# LightShaker-3.net
KiCad netlist of a schematic drawn in EAGLE
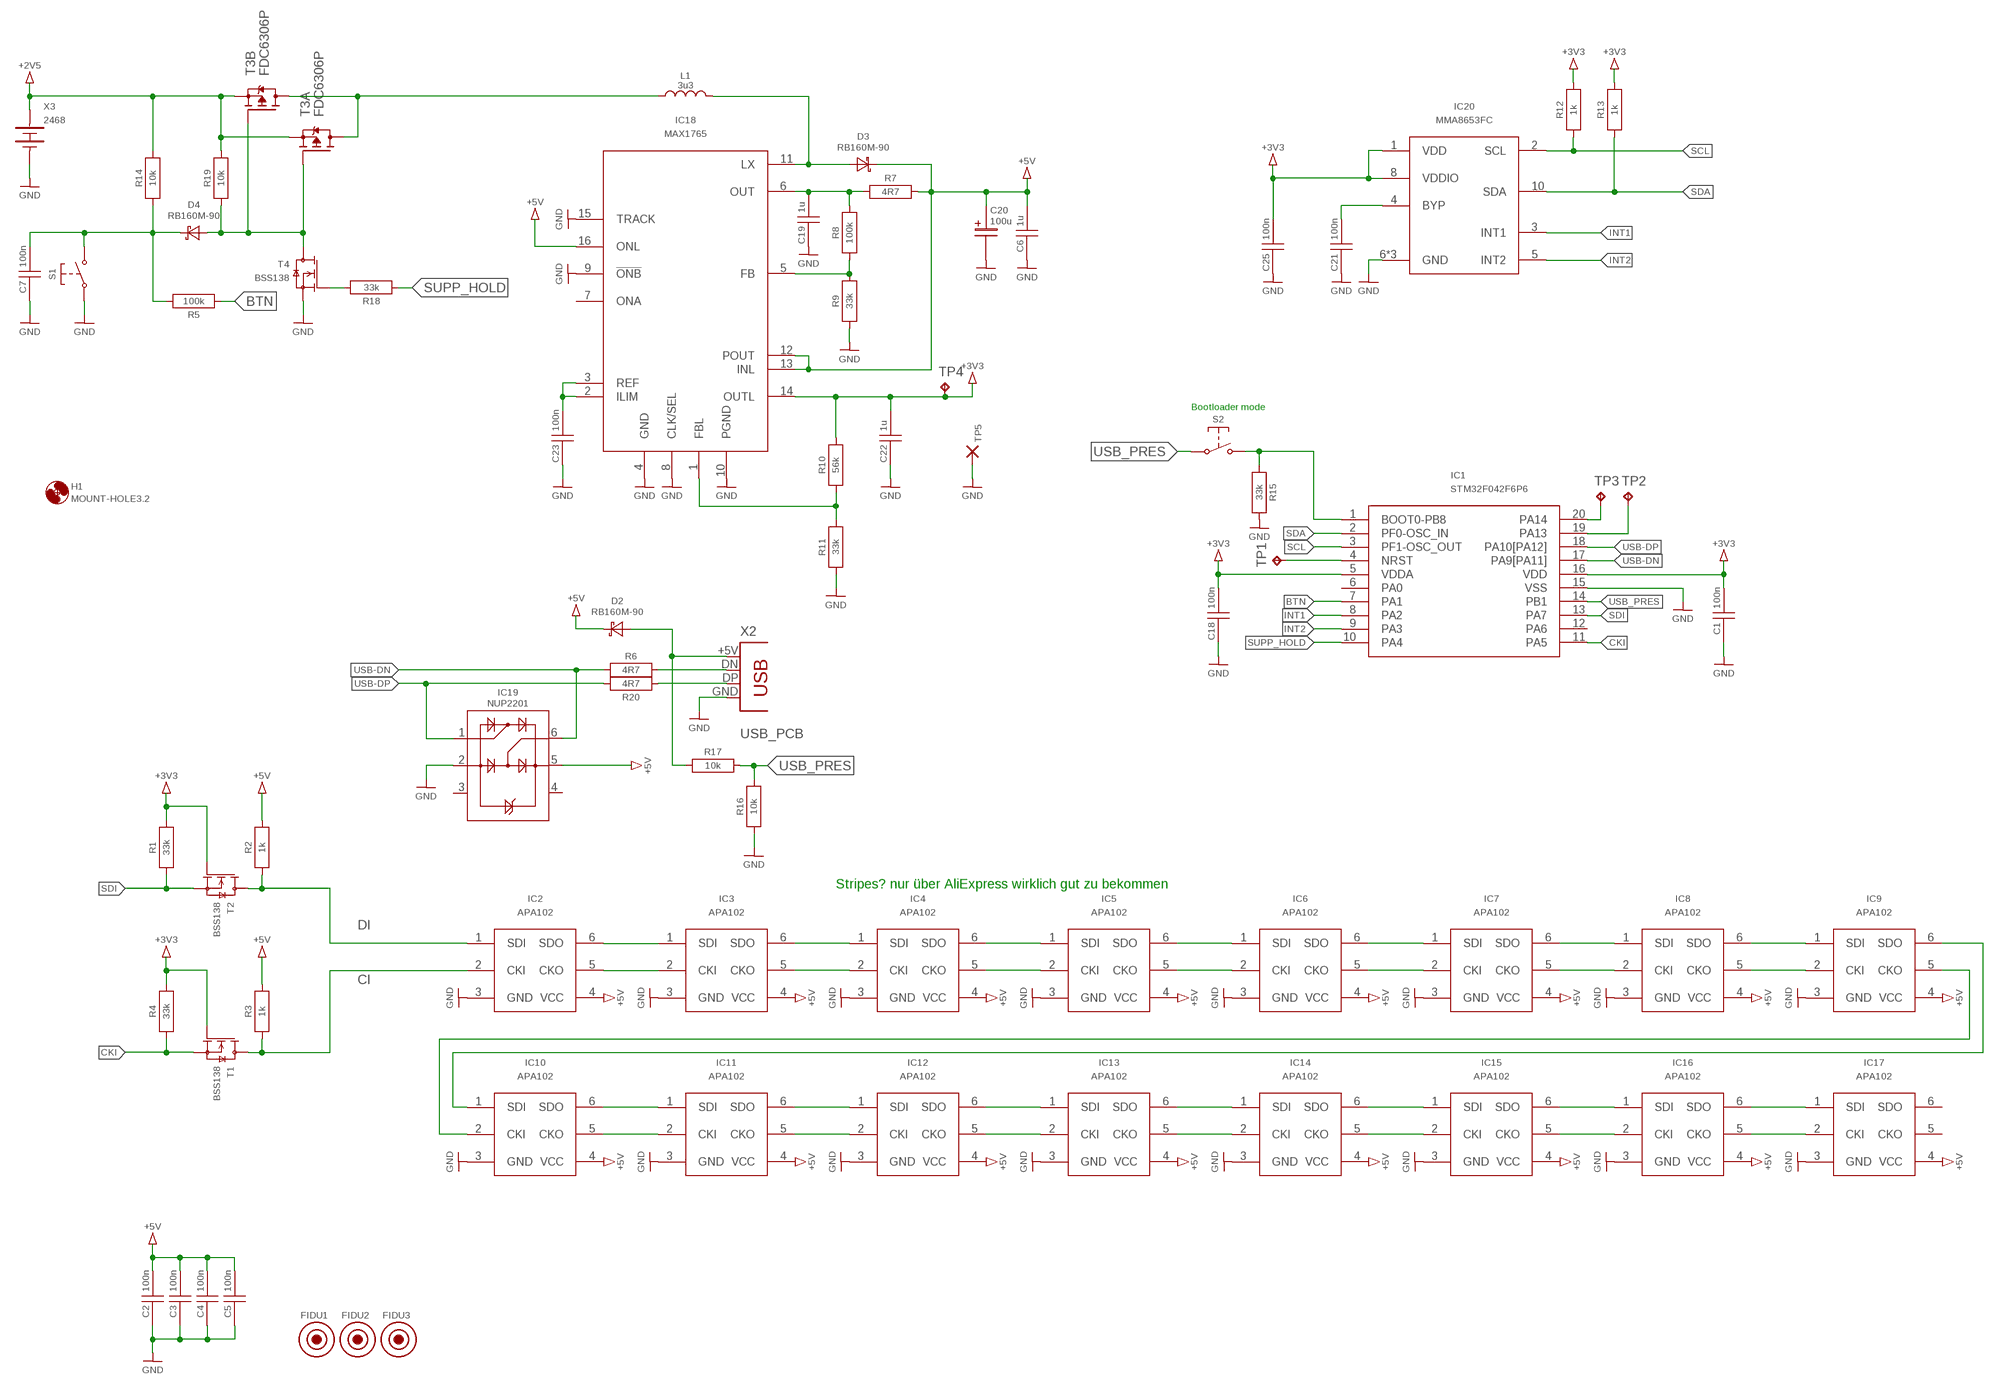
[diagram p0: schematic, sheet 1]

(export (version "E")
  (design (tool "Eeschema 10.0.6"))
  (components
    (comp (ref "C1")
      (value "100n")
      (footprint "eagle-import:SM_1206")
      (fields (field (name "MECHPART") "FALSE") (field (name "PARTNR") "E0001400"))
      (libsource (lib "eagle-import") (part "C1206"))
    )
    (comp (ref "C2")
      (value "100n")
      (footprint "eagle-import:SM_1206")
      (fields (field (name "MECHPART") "FALSE") (field (name "PARTNR") "E0001400"))
      (libsource (lib "eagle-import") (part "C1206"))
    )
    (comp (ref "C3")
      (value "100n")
      (footprint "eagle-import:SM_1206")
      (fields (field (name "MECHPART") "FALSE") (field (name "PARTNR") "E0001400"))
      (libsource (lib "eagle-import") (part "C1206"))
    )
    (comp (ref "C4")
      (value "100n")
      (footprint "eagle-import:SM_1206")
      (fields (field (name "MECHPART") "FALSE") (field (name "PARTNR") "E0001400"))
      (libsource (lib "eagle-import") (part "C1206"))
    )
    (comp (ref "C5")
      (value "100n")
      (footprint "eagle-import:SM_1206")
      (fields (field (name "MECHPART") "FALSE") (field (name "PARTNR") "E0001400"))
      (libsource (lib "eagle-import") (part "C1206"))
    )
    (comp (ref "C6")
      (value "1u")
      (footprint "eagle-import:SM_1206")
      (fields (field (name "MECHPART") "FALSE") (field (name "PARTNR") "E0487200"))
      (libsource (lib "eagle-import") (part "C1206"))
    )
    (comp (ref "C7")
      (value "100n")
      (footprint "eagle-import:SM_1206")
      (fields (field (name "MECHPART") "FALSE") (field (name "PARTNR") "E0001400"))
      (libsource (lib "eagle-import") (part "C1206"))
    )
    (comp (ref "C18")
      (value "100n")
      (footprint "eagle-import:SM_1206")
      (fields (field (name "MECHPART") "FALSE") (field (name "PARTNR") "E0001400"))
      (libsource (lib "eagle-import") (part "C1206"))
    )
    (comp (ref "C19")
      (value "1u")
      (footprint "eagle-import:SM_1206")
      (fields (field (name "MECHPART") "FALSE") (field (name "PARTNR") "E0487200"))
      (libsource (lib "eagle-import") (part "C1206"))
    )
    (comp (ref "C20")
      (value "100u")
      (footprint "eagle-import:SM_SIZE-D")
      (fields (field (name "MECHPART") "FALSE") (field (name "PARTNR") "E0242200"))
      (libsource (lib "eagle-import") (part "CPOLSIZE-D"))
    )
    (comp (ref "C21")
      (value "100n")
      (footprint "eagle-import:SM_1206")
      (fields (field (name "MECHPART") "FALSE") (field (name "PARTNR") "E0001400"))
      (libsource (lib "eagle-import") (part "C1206"))
    )
    (comp (ref "C22")
      (value "1u")
      (footprint "eagle-import:SM_1206")
      (fields (field (name "MECHPART") "FALSE") (field (name "PARTNR") "E0487200"))
      (libsource (lib "eagle-import") (part "C1206"))
    )
    (comp (ref "C23")
      (value "100n")
      (footprint "eagle-import:SM_1206")
      (fields (field (name "MECHPART") "FALSE") (field (name "PARTNR") "E0001400"))
      (libsource (lib "eagle-import") (part "C1206"))
    )
    (comp (ref "C25")
      (value "100n")
      (footprint "eagle-import:SM_1206")
      (fields (field (name "MECHPART") "FALSE") (field (name "PARTNR") "E0001400"))
      (libsource (lib "eagle-import") (part "C1206"))
    )
    (comp (ref "D2")
      (value "RB160M-90")
      (footprint "eagle-import:SM_SOD123_POL")
      (libsource (lib "eagle-import") (part "RB160M-90"))
    )
    (comp (ref "D3")
      (value "RB160M-90")
      (footprint "eagle-import:SM_SOD123_POL")
      (libsource (lib "eagle-import") (part "RB160M-90"))
    )
    (comp (ref "D4")
      (value "RB160M-90")
      (footprint "eagle-import:SM_SOD123_POL")
      (libsource (lib "eagle-import") (part "RB160M-90"))
    )
    (comp (ref "FIDU1")
      (value "FIDU_ROUND_NEW")
      (footprint "eagle-import:FIDUCIAL_LOETSTOPP")
      (libsource (lib "eagle-import") (part "FIDU_ROUND_NEW"))
    )
    (comp (ref "FIDU2")
      (value "FIDU_ROUND_NEW")
      (footprint "eagle-import:FIDUCIAL_LOETSTOPP")
      (libsource (lib "eagle-import") (part "FIDU_ROUND_NEW"))
    )
    (comp (ref "FIDU3")
      (value "FIDU_ROUND_NEW")
      (footprint "eagle-import:FIDUCIAL_LOETSTOPP")
      (libsource (lib "eagle-import") (part "FIDU_ROUND_NEW"))
    )
    (comp (ref "H1")
      (value "MOUNT-HOLE3.2")
      (footprint "eagle-import:3.2")
      (libsource (lib "eagle-import") (part "MOUNT-HOLE3.2"))
    )
    (comp (ref "IC1")
      (value "STM32F042F6P6")
      (footprint "eagle-import:SM_TSSOP20")
      (libsource (lib "eagle-import") (part "STM32F042F6P6"))
    )
    (comp (ref "IC2")
      (value "APA102")
      (footprint "eagle-import:SM_LED_PLCC6")
      (libsource (lib "eagle-import") (part "APA102"))
    )
    (comp (ref "IC3")
      (value "APA102")
      (footprint "eagle-import:SM_LED_PLCC6")
      (libsource (lib "eagle-import") (part "APA102"))
    )
    (comp (ref "IC4")
      (value "APA102")
      (footprint "eagle-import:SM_LED_PLCC6")
      (libsource (lib "eagle-import") (part "APA102"))
    )
    (comp (ref "IC5")
      (value "APA102")
      (footprint "eagle-import:SM_LED_PLCC6")
      (libsource (lib "eagle-import") (part "APA102"))
    )
    (comp (ref "IC6")
      (value "APA102")
      (footprint "eagle-import:SM_LED_PLCC6")
      (libsource (lib "eagle-import") (part "APA102"))
    )
    (comp (ref "IC7")
      (value "APA102")
      (footprint "eagle-import:SM_LED_PLCC6")
      (libsource (lib "eagle-import") (part "APA102"))
    )
    (comp (ref "IC8")
      (value "APA102")
      (footprint "eagle-import:SM_LED_PLCC6")
      (libsource (lib "eagle-import") (part "APA102"))
    )
    (comp (ref "IC9")
      (value "APA102")
      (footprint "eagle-import:SM_LED_PLCC6")
      (libsource (lib "eagle-import") (part "APA102"))
    )
    (comp (ref "IC10")
      (value "APA102")
      (footprint "eagle-import:SM_LED_PLCC6")
      (libsource (lib "eagle-import") (part "APA102"))
    )
    (comp (ref "IC11")
      (value "APA102")
      (footprint "eagle-import:SM_LED_PLCC6")
      (libsource (lib "eagle-import") (part "APA102"))
    )
    (comp (ref "IC12")
      (value "APA102")
      (footprint "eagle-import:SM_LED_PLCC6")
      (libsource (lib "eagle-import") (part "APA102"))
    )
    (comp (ref "IC13")
      (value "APA102")
      (footprint "eagle-import:SM_LED_PLCC6")
      (libsource (lib "eagle-import") (part "APA102"))
    )
    (comp (ref "IC14")
      (value "APA102")
      (footprint "eagle-import:SM_LED_PLCC6")
      (libsource (lib "eagle-import") (part "APA102"))
    )
    (comp (ref "IC15")
      (value "APA102")
      (footprint "eagle-import:SM_LED_PLCC6")
      (libsource (lib "eagle-import") (part "APA102"))
    )
    (comp (ref "IC16")
      (value "APA102")
      (footprint "eagle-import:SM_LED_PLCC6")
      (libsource (lib "eagle-import") (part "APA102"))
    )
    (comp (ref "IC17")
      (value "APA102")
      (footprint "eagle-import:SM_LED_PLCC6")
      (libsource (lib "eagle-import") (part "APA102"))
    )
    (comp (ref "IC18")
      (value "MAX1765")
      (footprint "eagle-import:SM_QSOP16")
      (libsource (lib "eagle-import") (part "MAX1765"))
    )
    (comp (ref "IC19")
      (value "NUP2201")
      (footprint "eagle-import:TSOP6")
      (libsource (lib "eagle-import") (part "NUP2201"))
    )
    (comp (ref "IC20")
      (value "MMA8653FC")
      (footprint "eagle-import:SM_DFN10")
      (libsource (lib "eagle-import") (part "MMA8653FC"))
    )
    (comp (ref "L1")
      (value "3u3")
      (footprint "eagle-import:SM_L_MOS6020")
      (libsource (lib "eagle-import") (part "L_MOS6020"))
    )
    (comp (ref "R1")
      (value "33k")
      (footprint "eagle-import:SM_1206")
      (fields (field (name "MECHPART") "FALSE") (field (name "PARTNR") "E0149800"))
      (libsource (lib "eagle-import") (part "R1206"))
    )
    (comp (ref "R2")
      (value "1k")
      (footprint "eagle-import:SM_1206")
      (fields (field (name "MECHPART") "FALSE") (field (name "PARTNR") "E0002500"))
      (libsource (lib "eagle-import") (part "R1206"))
    )
    (comp (ref "R3")
      (value "1k")
      (footprint "eagle-import:SM_1206")
      (fields (field (name "MECHPART") "FALSE") (field (name "PARTNR") "E0002500"))
      (libsource (lib "eagle-import") (part "R1206"))
    )
    (comp (ref "R4")
      (value "33k")
      (footprint "eagle-import:SM_1206")
      (fields (field (name "MECHPART") "FALSE") (field (name "PARTNR") "E0149800"))
      (libsource (lib "eagle-import") (part "R1206"))
    )
    (comp (ref "R5")
      (value "100k")
      (footprint "eagle-import:SM_1206")
      (fields (field (name "MECHPART") "FALSE"))
      (libsource (lib "eagle-import") (part "R1206"))
    )
    (comp (ref "R6")
      (value "4R7")
      (footprint "eagle-import:SM_1206")
      (fields (field (name "MECHPART") "FALSE"))
      (libsource (lib "eagle-import") (part "R1206"))
    )
    (comp (ref "R7")
      (value "4R7")
      (footprint "eagle-import:SM_1206")
      (fields (field (name "MECHPART") "FALSE") (field (name "PARTNR") "E0821300"))
      (libsource (lib "eagle-import") (part "R1206"))
    )
    (comp (ref "R8")
      (value "100k")
      (footprint "eagle-import:SM_1206")
      (fields (field (name "MECHPART") "FALSE") (field (name "PARTNR") "E0002800"))
      (libsource (lib "eagle-import") (part "R1206"))
    )
    (comp (ref "R9")
      (value "33k")
      (footprint "eagle-import:SM_1206")
      (fields (field (name "MECHPART") "FALSE") (field (name "PARTNR") "E0149800"))
      (libsource (lib "eagle-import") (part "R1206"))
    )
    (comp (ref "R10")
      (value "56k")
      (footprint "eagle-import:SM_1206")
      (fields (field (name "MECHPART") "FALSE"))
      (libsource (lib "eagle-import") (part "R1206"))
    )
    (comp (ref "R11")
      (value "33k")
      (footprint "eagle-import:SM_1206")
      (fields (field (name "MECHPART") "FALSE") (field (name "PARTNR") "E0149800"))
      (libsource (lib "eagle-import") (part "R1206"))
    )
    (comp (ref "R12")
      (value "1k")
      (footprint "eagle-import:SM_1206")
      (fields (field (name "MECHPART") "FALSE") (field (name "PARTNR") "E0002500"))
      (libsource (lib "eagle-import") (part "R1206"))
    )
    (comp (ref "R13")
      (value "1k")
      (footprint "eagle-import:SM_1206")
      (fields (field (name "MECHPART") "FALSE") (field (name "PARTNR") "E0002500"))
      (libsource (lib "eagle-import") (part "R1206"))
    )
    (comp (ref "R14")
      (value "10k")
      (footprint "eagle-import:SM_1206")
      (fields (field (name "MECHPART") "FALSE") (field (name "PARTNR") "E0002700"))
      (libsource (lib "eagle-import") (part "R1206"))
    )
    (comp (ref "R15")
      (value "33k")
      (footprint "eagle-import:SM_1206")
      (fields (field (name "MECHPART") "FALSE") (field (name "PARTNR") "E0149800"))
      (libsource (lib "eagle-import") (part "R1206"))
    )
    (comp (ref "R16")
      (value "10k")
      (footprint "eagle-import:SM_1206")
      (fields (field (name "MECHPART") "FALSE") (field (name "PARTNR") "E0002700"))
      (libsource (lib "eagle-import") (part "R1206"))
    )
    (comp (ref "R17")
      (value "10k")
      (footprint "eagle-import:SM_1206")
      (fields (field (name "MECHPART") "FALSE") (field (name "PARTNR") "E0002700"))
      (libsource (lib "eagle-import") (part "R1206"))
    )
    (comp (ref "R18")
      (value "33k")
      (footprint "eagle-import:SM_1206")
      (fields (field (name "MECHPART") "FALSE") (field (name "PARTNR") "E0149800"))
      (libsource (lib "eagle-import") (part "R1206"))
    )
    (comp (ref "R19")
      (value "10k")
      (footprint "eagle-import:SM_1206")
      (fields (field (name "MECHPART") "FALSE") (field (name "PARTNR") "E0002800"))
      (libsource (lib "eagle-import") (part "R1206"))
    )
    (comp (ref "R20")
      (value "4R7")
      (footprint "eagle-import:SM_1206")
      (fields (field (name "MECHPART") "FALSE"))
      (libsource (lib "eagle-import") (part "R1206"))
    )
    (comp (ref "S1")
      (value "PUSH-BUTTON_SMD")
      (footprint "eagle-import:PUSH-BUTTON_SMD")
      (libsource (lib "eagle-import") (part "PUSH-BUTTON_SMD"))
    )
    (comp (ref "S2")
      (value "PUSH-BUTTON_SMD")
      (footprint "eagle-import:PUSH-BUTTON_SMD")
      (libsource (lib "eagle-import") (part "PUSH-BUTTON_SMD"))
    )
    (comp (ref "T1")
      (value "BSS138")
      (footprint "eagle-import:SM_SOT23")
      (libsource (lib "eagle-import") (part "BSS138"))
    )
    (comp (ref "T2")
      (value "BSS138")
      (footprint "eagle-import:SM_SOT23")
      (libsource (lib "eagle-import") (part "BSS138"))
    )
    (comp (ref "T3")
      (value "FDC6306P")
      (footprint "eagle-import:TSOP6")
      (fields (field (name "PARTNR") "E0662100"))
      (libsource (lib "eagle-import") (part "FDC6306P"))
    )
    (comp (ref "T4")
      (value "BSS138")
      (footprint "eagle-import:SM_SOT23")
      (libsource (lib "eagle-import") (part "BSS138"))
    )
    (comp (ref "TP1")
      (value "TPTP12R")
      (footprint "eagle-import:TP12R")
      (libsource (lib "eagle-import") (part "TPTP12R"))
    )
    (comp (ref "TP2")
      (value "TPTP12R")
      (footprint "eagle-import:TP12R")
      (libsource (lib "eagle-import") (part "TPTP12R"))
    )
    (comp (ref "TP3")
      (value "TPTP12R")
      (footprint "eagle-import:TP12R")
      (libsource (lib "eagle-import") (part "TPTP12R"))
    )
    (comp (ref "TP4")
      (value "TPTP12R")
      (footprint "eagle-import:TP12R")
      (libsource (lib "eagle-import") (part "TPTP12R"))
    )
    (comp (ref "TP5")
      (value "CHECKER_1206")
      (footprint "eagle-import:SM_RCW_1206")
      (libsource (lib "eagle-import") (part "CHECKER_1206"))
    )
    (comp (ref "X2")
      (value "USB_PCB")
      (footprint "eagle-import:USB_PCB")
      (libsource (lib "eagle-import") (part "USB_PCB"))
    )
    (comp (ref "X3")
      (value "2468")
      (footprint "eagle-import:2468")
      (libsource (lib "eagle-import") (part "2468"))
    )
  )
  (nets
    (net (code "1") (name "+2V5") (class "Default")
      (node (ref "R14") (pin "2") (pinfunction "2_2") (pintype "bidirectional"))
      (node (ref "R19") (pin "2") (pinfunction "2_2") (pintype "bidirectional"))
      (node (ref "T3") (pin "2") (pinfunction "S_2") (pintype "passive"))
      (node (ref "T3") (pin "5") (pinfunction "S_5") (pintype "passive"))
      (node (ref "X3") (pin "POS") (pinfunction "POS_POS") (pintype "bidirectional"))
    )
    (net (code "2") (name "+3V3") (class "Default")
      (node (ref "C1") (pin "2") (pinfunction "2_2") (pintype "bidirectional"))
      (node (ref "C18") (pin "2") (pinfunction "2_2") (pintype "bidirectional"))
      (node (ref "C22") (pin "2") (pinfunction "2_2") (pintype "bidirectional"))
      (node (ref "C25") (pin "2") (pinfunction "2_2") (pintype "bidirectional"))
      (node (ref "IC1") (pin "16") (pinfunction "VDD_16") (pintype "bidirectional"))
      (node (ref "IC1") (pin "5") (pinfunction "VDDA_5") (pintype "bidirectional"))
      (node (ref "IC18") (pin "14") (pinfunction "OUTL_14") (pintype "bidirectional"))
      (node (ref "IC20") (pin "1") (pinfunction "VDD_1") (pintype "bidirectional"))
      (node (ref "IC20") (pin "8") (pinfunction "VDDIO_8") (pintype "bidirectional"))
      (node (ref "R1") (pin "2") (pinfunction "2_2") (pintype "bidirectional"))
      (node (ref "R10") (pin "2") (pinfunction "2_2") (pintype "bidirectional"))
      (node (ref "R12") (pin "2") (pinfunction "2_2") (pintype "bidirectional"))
      (node (ref "R13") (pin "2") (pinfunction "2_2") (pintype "bidirectional"))
      (node (ref "R4") (pin "2") (pinfunction "2_2") (pintype "bidirectional"))
      (node (ref "T1") (pin "1") (pinfunction "G_1") (pintype "bidirectional"))
      (node (ref "T2") (pin "1") (pinfunction "G_1") (pintype "bidirectional"))
      (node (ref "TP4") (pin "TP") (pinfunction "TP_TP") (pintype "input"))
    )
    (net (code "3") (name "+5V") (class "Default")
      (node (ref "C2") (pin "2") (pinfunction "2_2") (pintype "bidirectional"))
      (node (ref "C20") (pin "POS") (pinfunction "POS_POS") (pintype "bidirectional"))
      (node (ref "C3") (pin "2") (pinfunction "2_2") (pintype "bidirectional"))
      (node (ref "C4") (pin "2") (pinfunction "2_2") (pintype "bidirectional"))
      (node (ref "C5") (pin "2") (pinfunction "2_2") (pintype "bidirectional"))
      (node (ref "C6") (pin "2") (pinfunction "2_2") (pintype "bidirectional"))
      (node (ref "D2") (pin "C") (pinfunction "C_C") (pintype "bidirectional"))
      (node (ref "D3") (pin "C") (pinfunction "C_C") (pintype "bidirectional"))
      (node (ref "IC10") (pin "4") (pinfunction "VCC_4") (pintype "bidirectional"))
      (node (ref "IC11") (pin "4") (pinfunction "VCC_4") (pintype "bidirectional"))
      (node (ref "IC12") (pin "4") (pinfunction "VCC_4") (pintype "bidirectional"))
      (node (ref "IC13") (pin "4") (pinfunction "VCC_4") (pintype "bidirectional"))
      (node (ref "IC14") (pin "4") (pinfunction "VCC_4") (pintype "bidirectional"))
      (node (ref "IC15") (pin "4") (pinfunction "VCC_4") (pintype "bidirectional"))
      (node (ref "IC16") (pin "4") (pinfunction "VCC_4") (pintype "bidirectional"))
      (node (ref "IC17") (pin "4") (pinfunction "VCC_4") (pintype "bidirectional"))
      (node (ref "IC18") (pin "12") (pinfunction "POUT_12") (pintype "bidirectional"))
      (node (ref "IC18") (pin "13") (pinfunction "INL_13") (pintype "bidirectional"))
      (node (ref "IC18") (pin "16") (pinfunction "ONL_16") (pintype "bidirectional"))
      (node (ref "IC19") (pin "5") (pinfunction "VP_5") (pintype "bidirectional"))
      (node (ref "IC2") (pin "4") (pinfunction "VCC_4") (pintype "bidirectional"))
      (node (ref "IC3") (pin "4") (pinfunction "VCC_4") (pintype "bidirectional"))
      (node (ref "IC4") (pin "4") (pinfunction "VCC_4") (pintype "bidirectional"))
      (node (ref "IC5") (pin "4") (pinfunction "VCC_4") (pintype "bidirectional"))
      (node (ref "IC6") (pin "4") (pinfunction "VCC_4") (pintype "bidirectional"))
      (node (ref "IC7") (pin "4") (pinfunction "VCC_4") (pintype "bidirectional"))
      (node (ref "IC8") (pin "4") (pinfunction "VCC_4") (pintype "bidirectional"))
      (node (ref "IC9") (pin "4") (pinfunction "VCC_4") (pintype "bidirectional"))
      (node (ref "R2") (pin "2") (pinfunction "2_2") (pintype "bidirectional"))
      (node (ref "R3") (pin "2") (pinfunction "2_2") (pintype "bidirectional"))
      (node (ref "R7") (pin "2") (pinfunction "2_2") (pintype "bidirectional"))
    )
    (net (code "4") (name "/CI") (class "Default")
      (node (ref "IC2") (pin "2") (pinfunction "CKI_2") (pintype "bidirectional"))
      (node (ref "R3") (pin "1") (pinfunction "1_1") (pintype "bidirectional"))
      (node (ref "T1") (pin "3") (pinfunction "D_3") (pintype "bidirectional"))
    )
    (net (code "5") (name "/DI") (class "Default")
      (node (ref "IC2") (pin "1") (pinfunction "SDI_1") (pintype "bidirectional"))
      (node (ref "R2") (pin "1") (pinfunction "1_1") (pintype "bidirectional"))
      (node (ref "T2") (pin "3") (pinfunction "D_3") (pintype "bidirectional"))
    )
    (net (code "6") (name "BTN") (class "Default")
      (node (ref "IC1") (pin "7") (pinfunction "PA1_7") (pintype "bidirectional"))
      (node (ref "R5") (pin "1") (pinfunction "1_1") (pintype "bidirectional"))
    )
    (net (code "7") (name "CKI") (class "Default")
      (node (ref "IC1") (pin "11") (pinfunction "PA5_11") (pintype "bidirectional"))
      (node (ref "R4") (pin "1") (pinfunction "1_1") (pintype "bidirectional"))
      (node (ref "T1") (pin "2") (pinfunction "S_2") (pintype "bidirectional"))
    )
    (net (code "8") (name "GND") (class "Default")
      (node (ref "C1") (pin "1") (pinfunction "1_1") (pintype "bidirectional"))
      (node (ref "C18") (pin "1") (pinfunction "1_1") (pintype "bidirectional"))
      (node (ref "C19") (pin "1") (pinfunction "1_1") (pintype "bidirectional"))
      (node (ref "C2") (pin "1") (pinfunction "1_1") (pintype "bidirectional"))
      (node (ref "C20") (pin "NEG") (pinfunction "NEG_NEG") (pintype "bidirectional"))
      (node (ref "C21") (pin "1") (pinfunction "1_1") (pintype "bidirectional"))
      (node (ref "C22") (pin "1") (pinfunction "1_1") (pintype "bidirectional"))
      (node (ref "C23") (pin "1") (pinfunction "1_1") (pintype "bidirectional"))
      (node (ref "C25") (pin "1") (pinfunction "1_1") (pintype "bidirectional"))
      (node (ref "C3") (pin "1") (pinfunction "1_1") (pintype "bidirectional"))
      (node (ref "C4") (pin "1") (pinfunction "1_1") (pintype "bidirectional"))
      (node (ref "C5") (pin "1") (pinfunction "1_1") (pintype "bidirectional"))
      (node (ref "C6") (pin "1") (pinfunction "1_1") (pintype "bidirectional"))
      (node (ref "C7") (pin "1") (pinfunction "1_1") (pintype "bidirectional"))
      (node (ref "IC1") (pin "15") (pinfunction "VSS_15") (pintype "bidirectional"))
      (node (ref "IC10") (pin "3") (pinfunction "GND_3") (pintype "bidirectional"))
      (node (ref "IC11") (pin "3") (pinfunction "GND_3") (pintype "bidirectional"))
      (node (ref "IC12") (pin "3") (pinfunction "GND_3") (pintype "bidirectional"))
      (node (ref "IC13") (pin "3") (pinfunction "GND_3") (pintype "bidirectional"))
      (node (ref "IC14") (pin "3") (pinfunction "GND_3") (pintype "bidirectional"))
      (node (ref "IC15") (pin "3") (pinfunction "GND_3") (pintype "bidirectional"))
      (node (ref "IC16") (pin "3") (pinfunction "GND_3") (pintype "bidirectional"))
      (node (ref "IC17") (pin "3") (pinfunction "GND_3") (pintype "bidirectional"))
      (node (ref "IC18") (pin "10") (pinfunction "PGND_10") (pintype "bidirectional"))
      (node (ref "IC18") (pin "15") (pinfunction "TRACK_15") (pintype "bidirectional"))
      (node (ref "IC18") (pin "4") (pinfunction "GND_4") (pintype "bidirectional"))
      (node (ref "IC18") (pin "8") (pinfunction "CLK/SEL_8") (pintype "bidirectional"))
      (node (ref "IC18") (pin "9") (pinfunction "~{ONB}_9") (pintype "bidirectional"))
      (node (ref "IC19") (pin "2") (pinfunction "GND_2") (pintype "bidirectional"))
      (node (ref "IC2") (pin "3") (pinfunction "GND_3") (pintype "bidirectional"))
      (node (ref "IC20") (pin "6") (pinfunction "GND_6") (pintype "bidirectional"))
      (node (ref "IC20") (pin "7") (pinfunction "GND_7") (pintype "bidirectional"))
      (node (ref "IC20") (pin "9") (pinfunction "GND_9") (pintype "bidirectional"))
      (node (ref "IC3") (pin "3") (pinfunction "GND_3") (pintype "bidirectional"))
      (node (ref "IC4") (pin "3") (pinfunction "GND_3") (pintype "bidirectional"))
      (node (ref "IC5") (pin "3") (pinfunction "GND_3") (pintype "bidirectional"))
      (node (ref "IC6") (pin "3") (pinfunction "GND_3") (pintype "bidirectional"))
      (node (ref "IC7") (pin "3") (pinfunction "GND_3") (pintype "bidirectional"))
      (node (ref "IC8") (pin "3") (pinfunction "GND_3") (pintype "bidirectional"))
      (node (ref "IC9") (pin "3") (pinfunction "GND_3") (pintype "bidirectional"))
      (node (ref "R11") (pin "1") (pinfunction "1_1") (pintype "bidirectional"))
      (node (ref "R15") (pin "2") (pinfunction "2_2") (pintype "bidirectional"))
      (node (ref "R16") (pin "1") (pinfunction "1_1") (pintype "bidirectional"))
      (node (ref "R9") (pin "1") (pinfunction "1_1") (pintype "bidirectional"))
      (node (ref "S1") (pin "1") (pinfunction "P_1") (pintype "passive"))
      (node (ref "S1") (pin "2") (pinfunction "P_2") (pintype "passive"))
      (node (ref "T4") (pin "2") (pinfunction "S_2") (pintype "bidirectional"))
      (node (ref "TP5") (pin "1") (pinfunction "P_1") (pintype "passive"))
      (node (ref "X2") (pin "GND") (pinfunction "GND_GND") (pintype "passive"))
      (node (ref "X3") (pin "NEG") (pinfunction "NEG_NEG") (pintype "bidirectional"))
    )
    (net (code "9") (name "INT1") (class "Default")
      (node (ref "IC1") (pin "8") (pinfunction "PA2_8") (pintype "bidirectional"))
      (node (ref "IC20") (pin "3") (pinfunction "INT1_3") (pintype "bidirectional"))
    )
    (net (code "10") (name "INT2") (class "Default")
      (node (ref "IC1") (pin "9") (pinfunction "PA3_9") (pintype "bidirectional"))
      (node (ref "IC20") (pin "5") (pinfunction "INT2_5") (pintype "bidirectional"))
    )
    (net (code "11") (name "Net-(C7-Pad2)") (class "Default")
      (node (ref "C7") (pin "2") (pinfunction "2_2") (pintype "bidirectional"))
      (node (ref "D4") (pin "C") (pinfunction "C_C") (pintype "bidirectional"))
      (node (ref "R14") (pin "1") (pinfunction "1_1") (pintype "bidirectional"))
      (node (ref "R5") (pin "2") (pinfunction "2_2") (pintype "bidirectional"))
      (node (ref "S1") (pin "3") (pinfunction "S_3") (pintype "passive"))
      (node (ref "S1") (pin "4") (pinfunction "S_4") (pintype "passive"))
    )
    (net (code "12") (name "Net-(D2-PadA)") (class "Default")
      (node (ref "D2") (pin "A") (pinfunction "A_A") (pintype "bidirectional"))
      (node (ref "R17") (pin "1") (pinfunction "1_1") (pintype "bidirectional"))
      (node (ref "X2") (pin "+5V") (pinfunction "+5V_+5V") (pintype "passive"))
    )
    (net (code "13") (name "Net-(IC1-BOOT0-PB8)") (class "Default")
      (node (ref "IC1") (pin "1") (pinfunction "BOOT0-PB8_1") (pintype "bidirectional"))
      (node (ref "R15") (pin "1") (pinfunction "1_1") (pintype "bidirectional"))
      (node (ref "S2") (pin "3") (pinfunction "S_3") (pintype "passive"))
      (node (ref "S2") (pin "4") (pinfunction "S_4") (pintype "passive"))
    )
    (net (code "14") (name "Net-(IC1-NRST)") (class "Default")
      (node (ref "IC1") (pin "4") (pinfunction "NRST_4") (pintype "bidirectional"))
      (node (ref "TP1") (pin "TP") (pinfunction "TP_TP") (pintype "input"))
    )
    (net (code "15") (name "Net-(IC1-PA13)") (class "Default")
      (node (ref "IC1") (pin "19") (pinfunction "PA13_19") (pintype "bidirectional"))
      (node (ref "TP2") (pin "TP") (pinfunction "TP_TP") (pintype "input"))
    )
    (net (code "16") (name "Net-(IC1-PA14)") (class "Default")
      (node (ref "IC1") (pin "20") (pinfunction "PA14_20") (pintype "bidirectional"))
      (node (ref "TP3") (pin "TP") (pinfunction "TP_TP") (pintype "input"))
    )
    (net (code "17") (name "Net-(IC2-CKO)") (class "Default")
      (node (ref "IC2") (pin "5") (pinfunction "CKO_5") (pintype "bidirectional"))
      (node (ref "IC3") (pin "2") (pinfunction "CKI_2") (pintype "bidirectional"))
    )
    (net (code "18") (name "Net-(IC2-SDO)") (class "Default")
      (node (ref "IC2") (pin "6") (pinfunction "SDO_6") (pintype "bidirectional"))
      (node (ref "IC3") (pin "1") (pinfunction "SDI_1") (pintype "bidirectional"))
    )
    (net (code "19") (name "Net-(IC3-CKO)") (class "Default")
      (node (ref "IC3") (pin "5") (pinfunction "CKO_5") (pintype "bidirectional"))
      (node (ref "IC4") (pin "2") (pinfunction "CKI_2") (pintype "bidirectional"))
    )
    (net (code "20") (name "Net-(IC3-SDO)") (class "Default")
      (node (ref "IC3") (pin "6") (pinfunction "SDO_6") (pintype "bidirectional"))
      (node (ref "IC4") (pin "1") (pinfunction "SDI_1") (pintype "bidirectional"))
    )
    (net (code "21") (name "Net-(IC4-CKO)") (class "Default")
      (node (ref "IC4") (pin "5") (pinfunction "CKO_5") (pintype "bidirectional"))
      (node (ref "IC5") (pin "2") (pinfunction "CKI_2") (pintype "bidirectional"))
    )
    (net (code "22") (name "Net-(IC4-SDO)") (class "Default")
      (node (ref "IC4") (pin "6") (pinfunction "SDO_6") (pintype "bidirectional"))
      (node (ref "IC5") (pin "1") (pinfunction "SDI_1") (pintype "bidirectional"))
    )
    (net (code "23") (name "Net-(IC5-CKO)") (class "Default")
      (node (ref "IC5") (pin "5") (pinfunction "CKO_5") (pintype "bidirectional"))
      (node (ref "IC6") (pin "2") (pinfunction "CKI_2") (pintype "bidirectional"))
    )
    (net (code "24") (name "Net-(IC5-SDO)") (class "Default")
      (node (ref "IC5") (pin "6") (pinfunction "SDO_6") (pintype "bidirectional"))
      (node (ref "IC6") (pin "1") (pinfunction "SDI_1") (pintype "bidirectional"))
    )
    (net (code "25") (name "Net-(IC6-CKO)") (class "Default")
      (node (ref "IC6") (pin "5") (pinfunction "CKO_5") (pintype "bidirectional"))
      (node (ref "IC7") (pin "2") (pinfunction "CKI_2") (pintype "bidirectional"))
    )
    (net (code "26") (name "Net-(IC6-SDO)") (class "Default")
      (node (ref "IC6") (pin "6") (pinfunction "SDO_6") (pintype "bidirectional"))
      (node (ref "IC7") (pin "1") (pinfunction "SDI_1") (pintype "bidirectional"))
    )
    (net (code "27") (name "Net-(IC7-CKO)") (class "Default")
      (node (ref "IC7") (pin "5") (pinfunction "CKO_5") (pintype "bidirectional"))
      (node (ref "IC8") (pin "2") (pinfunction "CKI_2") (pintype "bidirectional"))
    )
    (net (code "28") (name "Net-(IC7-SDO)") (class "Default")
      (node (ref "IC7") (pin "6") (pinfunction "SDO_6") (pintype "bidirectional"))
      (node (ref "IC8") (pin "1") (pinfunction "SDI_1") (pintype "bidirectional"))
    )
    (net (code "29") (name "Net-(IC8-CKO)") (class "Default")
      (node (ref "IC8") (pin "5") (pinfunction "CKO_5") (pintype "bidirectional"))
      (node (ref "IC9") (pin "2") (pinfunction "CKI_2") (pintype "bidirectional"))
    )
    (net (code "30") (name "Net-(IC8-SDO)") (class "Default")
      (node (ref "IC8") (pin "6") (pinfunction "SDO_6") (pintype "bidirectional"))
      (node (ref "IC9") (pin "1") (pinfunction "SDI_1") (pintype "bidirectional"))
    )
    (net (code "31") (name "Net-(IC10-CKI)") (class "Default")
      (node (ref "IC10") (pin "2") (pinfunction "CKI_2") (pintype "bidirectional"))
      (node (ref "IC9") (pin "5") (pinfunction "CKO_5") (pintype "bidirectional"))
    )
    (net (code "32") (name "Net-(IC10-CKO)") (class "Default")
      (node (ref "IC10") (pin "5") (pinfunction "CKO_5") (pintype "bidirectional"))
      (node (ref "IC11") (pin "2") (pinfunction "CKI_2") (pintype "bidirectional"))
    )
    (net (code "33") (name "Net-(IC10-SDI)") (class "Default")
      (node (ref "IC10") (pin "1") (pinfunction "SDI_1") (pintype "bidirectional"))
      (node (ref "IC9") (pin "6") (pinfunction "SDO_6") (pintype "bidirectional"))
    )
    (net (code "34") (name "Net-(IC10-SDO)") (class "Default")
      (node (ref "IC10") (pin "6") (pinfunction "SDO_6") (pintype "bidirectional"))
      (node (ref "IC11") (pin "1") (pinfunction "SDI_1") (pintype "bidirectional"))
    )
    (net (code "35") (name "Net-(IC11-CKO)") (class "Default")
      (node (ref "IC11") (pin "5") (pinfunction "CKO_5") (pintype "bidirectional"))
      (node (ref "IC12") (pin "2") (pinfunction "CKI_2") (pintype "bidirectional"))
    )
    (net (code "36") (name "Net-(IC11-SDO)") (class "Default")
      (node (ref "IC11") (pin "6") (pinfunction "SDO_6") (pintype "bidirectional"))
      (node (ref "IC12") (pin "1") (pinfunction "SDI_1") (pintype "bidirectional"))
    )
    (net (code "37") (name "Net-(IC12-CKO)") (class "Default")
      (node (ref "IC12") (pin "5") (pinfunction "CKO_5") (pintype "bidirectional"))
      (node (ref "IC13") (pin "2") (pinfunction "CKI_2") (pintype "bidirectional"))
    )
    (net (code "38") (name "Net-(IC12-SDO)") (class "Default")
      (node (ref "IC12") (pin "6") (pinfunction "SDO_6") (pintype "bidirectional"))
      (node (ref "IC13") (pin "1") (pinfunction "SDI_1") (pintype "bidirectional"))
    )
    (net (code "39") (name "Net-(IC13-CKO)") (class "Default")
      (node (ref "IC13") (pin "5") (pinfunction "CKO_5") (pintype "bidirectional"))
      (node (ref "IC14") (pin "2") (pinfunction "CKI_2") (pintype "bidirectional"))
    )
    (net (code "40") (name "Net-(IC13-SDO)") (class "Default")
      (node (ref "IC13") (pin "6") (pinfunction "SDO_6") (pintype "bidirectional"))
      (node (ref "IC14") (pin "1") (pinfunction "SDI_1") (pintype "bidirectional"))
    )
    (net (code "41") (name "Net-(IC14-CKO)") (class "Default")
      (node (ref "IC14") (pin "5") (pinfunction "CKO_5") (pintype "bidirectional"))
      (node (ref "IC15") (pin "2") (pinfunction "CKI_2") (pintype "bidirectional"))
    )
    (net (code "42") (name "Net-(IC14-SDO)") (class "Default")
      (node (ref "IC14") (pin "6") (pinfunction "SDO_6") (pintype "bidirectional"))
      (node (ref "IC15") (pin "1") (pinfunction "SDI_1") (pintype "bidirectional"))
    )
    (net (code "43") (name "Net-(IC15-CKO)") (class "Default")
      (node (ref "IC15") (pin "5") (pinfunction "CKO_5") (pintype "bidirectional"))
      (node (ref "IC16") (pin "2") (pinfunction "CKI_2") (pintype "bidirectional"))
    )
    (net (code "44") (name "Net-(IC15-SDO)") (class "Default")
      (node (ref "IC15") (pin "6") (pinfunction "SDO_6") (pintype "bidirectional"))
      (node (ref "IC16") (pin "1") (pinfunction "SDI_1") (pintype "bidirectional"))
    )
    (net (code "45") (name "Net-(IC16-CKO)") (class "Default")
      (node (ref "IC16") (pin "5") (pinfunction "CKO_5") (pintype "bidirectional"))
      (node (ref "IC17") (pin "2") (pinfunction "CKI_2") (pintype "bidirectional"))
    )
    (net (code "46") (name "Net-(IC16-SDO)") (class "Default")
      (node (ref "IC16") (pin "6") (pinfunction "SDO_6") (pintype "bidirectional"))
      (node (ref "IC17") (pin "1") (pinfunction "SDI_1") (pintype "bidirectional"))
    )
    (net (code "47") (name "Net-(IC18-FB)") (class "Default")
      (node (ref "IC18") (pin "5") (pinfunction "FB_5") (pintype "bidirectional"))
      (node (ref "R8") (pin "1") (pinfunction "1_1") (pintype "bidirectional"))
      (node (ref "R9") (pin "2") (pinfunction "2_2") (pintype "bidirectional"))
    )
    (net (code "48") (name "Net-(IC18-FBL)") (class "Default")
      (node (ref "IC18") (pin "1") (pinfunction "FBL_1") (pintype "bidirectional"))
      (node (ref "R10") (pin "1") (pinfunction "1_1") (pintype "bidirectional"))
      (node (ref "R11") (pin "2") (pinfunction "2_2") (pintype "bidirectional"))
    )
    (net (code "49") (name "Net-(IC18-ILIM)") (class "Default")
      (node (ref "C23") (pin "2") (pinfunction "2_2") (pintype "bidirectional"))
      (node (ref "IC18") (pin "2") (pinfunction "ILIM_2") (pintype "bidirectional"))
      (node (ref "IC18") (pin "3") (pinfunction "REF_3") (pintype "bidirectional"))
    )
    (net (code "50") (name "Net-(IC18-LX)") (class "Default")
      (node (ref "D3") (pin "A") (pinfunction "A_A") (pintype "bidirectional"))
      (node (ref "IC18") (pin "11") (pinfunction "LX_11") (pintype "bidirectional"))
      (node (ref "L1") (pin "2") (pinfunction "2_2") (pintype "bidirectional"))
    )
    (net (code "51") (name "Net-(IC18-OUT)") (class "Default")
      (node (ref "C19") (pin "2") (pinfunction "2_2") (pintype "bidirectional"))
      (node (ref "IC18") (pin "6") (pinfunction "OUT_6") (pintype "bidirectional"))
      (node (ref "R7") (pin "1") (pinfunction "1_1") (pintype "bidirectional"))
      (node (ref "R8") (pin "2") (pinfunction "2_2") (pintype "bidirectional"))
    )
    (net (code "52") (name "Net-(IC20-BYP)") (class "Default")
      (node (ref "C21") (pin "2") (pinfunction "2_2") (pintype "bidirectional"))
      (node (ref "IC20") (pin "4") (pinfunction "BYP_4") (pintype "bidirectional"))
    )
    (net (code "53") (name "Net-(R6-Pad2)") (class "Default")
      (node (ref "R6") (pin "2") (pinfunction "2_2") (pintype "bidirectional"))
      (node (ref "X2") (pin "DN") (pinfunction "DN_DN") (pintype "passive"))
    )
    (net (code "54") (name "Net-(R20-Pad1)") (class "Default")
      (node (ref "R20") (pin "1") (pinfunction "1_1") (pintype "bidirectional"))
      (node (ref "X2") (pin "DP") (pinfunction "DP_DP") (pintype "passive"))
    )
    (net (code "55") (name "Net-(T3A-D)") (class "Default")
      (node (ref "L1") (pin "1") (pinfunction "1_1") (pintype "bidirectional"))
      (node (ref "T3") (pin "4") (pinfunction "D_4") (pintype "passive"))
      (node (ref "T3") (pin "6") (pinfunction "D_6") (pintype "passive"))
    )
    (net (code "56") (name "Net-(T3A-G)") (class "Default")
      (node (ref "D4") (pin "A") (pinfunction "A_A") (pintype "bidirectional"))
      (node (ref "R19") (pin "1") (pinfunction "1_1") (pintype "bidirectional"))
      (node (ref "T3") (pin "1") (pinfunction "G_1") (pintype "passive"))
      (node (ref "T3") (pin "3") (pinfunction "G_3") (pintype "passive"))
      (node (ref "T4") (pin "3") (pinfunction "D_3") (pintype "bidirectional"))
    )
    (net (code "57") (name "Net-(T4-G)") (class "Default")
      (node (ref "R18") (pin "2") (pinfunction "2_2") (pintype "bidirectional"))
      (node (ref "T4") (pin "1") (pinfunction "G_1") (pintype "bidirectional"))
    )
    (net (code "58") (name "SCL") (class "Default")
      (node (ref "IC1") (pin "3") (pinfunction "PF1-OSC_OUT_3") (pintype "bidirectional"))
      (node (ref "IC20") (pin "2") (pinfunction "SCL_2") (pintype "bidirectional"))
      (node (ref "R12") (pin "1") (pinfunction "1_1") (pintype "bidirectional"))
    )
    (net (code "59") (name "SDA") (class "Default")
      (node (ref "IC1") (pin "2") (pinfunction "PF0-OSC_IN_2") (pintype "bidirectional"))
      (node (ref "IC20") (pin "10") (pinfunction "SDA_10") (pintype "bidirectional"))
      (node (ref "R13") (pin "1") (pinfunction "1_1") (pintype "bidirectional"))
    )
    (net (code "60") (name "SDI") (class "Default")
      (node (ref "IC1") (pin "13") (pinfunction "PA7_13") (pintype "bidirectional"))
      (node (ref "R1") (pin "1") (pinfunction "1_1") (pintype "bidirectional"))
      (node (ref "T2") (pin "2") (pinfunction "S_2") (pintype "bidirectional"))
    )
    (net (code "61") (name "SUPP_HOLD") (class "Default")
      (node (ref "IC1") (pin "10") (pinfunction "PA4_10") (pintype "bidirectional"))
      (node (ref "R18") (pin "1") (pinfunction "1_1") (pintype "bidirectional"))
    )
    (net (code "62") (name "USB-DN") (class "Default")
      (node (ref "IC1") (pin "17") (pinfunction "PA9[PA11]_17") (pintype "bidirectional"))
      (node (ref "IC19") (pin "6") (pinfunction "IO2_6") (pintype "bidirectional"))
      (node (ref "R6") (pin "1") (pinfunction "1_1") (pintype "bidirectional"))
    )
    (net (code "63") (name "USB-DP") (class "Default")
      (node (ref "IC1") (pin "18") (pinfunction "PA10[PA12]_18") (pintype "bidirectional"))
      (node (ref "IC19") (pin "1") (pinfunction "IO1_1") (pintype "bidirectional"))
      (node (ref "R20") (pin "2") (pinfunction "2_2") (pintype "bidirectional"))
    )
    (net (code "64") (name "USB_PRES") (class "Default")
      (node (ref "IC1") (pin "14") (pinfunction "PB1_14") (pintype "bidirectional"))
      (node (ref "R16") (pin "2") (pinfunction "2_2") (pintype "bidirectional"))
      (node (ref "R17") (pin "2") (pinfunction "2_2") (pintype "bidirectional"))
      (node (ref "S2") (pin "1") (pinfunction "P_1") (pintype "passive"))
      (node (ref "S2") (pin "2") (pinfunction "P_2") (pintype "passive"))
    )
    (net (code "65") (name "unconnected-(IC1-PA0-Pad6)") (class "Default")
      (node (ref "IC1") (pin "6") (pinfunction "PA0_6") (pintype "bidirectional"))
    )
    (net (code "66") (name "unconnected-(IC1-PA6-Pad12)") (class "Default")
      (node (ref "IC1") (pin "12") (pinfunction "PA6_12") (pintype "bidirectional"))
    )
    (net (code "67") (name "unconnected-(IC17-CKO-Pad5)") (class "Default")
      (node (ref "IC17") (pin "5") (pinfunction "CKO_5") (pintype "bidirectional"))
    )
    (net (code "68") (name "unconnected-(IC17-SDO-Pad6)") (class "Default")
      (node (ref "IC17") (pin "6") (pinfunction "SDO_6") (pintype "bidirectional"))
    )
    (net (code "69") (name "unconnected-(IC18-ONA-Pad7)") (class "Default")
      (node (ref "IC18") (pin "7") (pinfunction "ONA_7") (pintype "bidirectional"))
    )
    (net (code "70") (name "unconnected-(IC19-NC1-Pad3)") (class "Default")
      (node (ref "IC19") (pin "3") (pinfunction "NC1_3") (pintype "bidirectional"))
    )
    (net (code "71") (name "unconnected-(IC19-NC2-Pad4)") (class "Default")
      (node (ref "IC19") (pin "4") (pinfunction "NC2_4") (pintype "bidirectional"))
    )
  )
)
